# Sensing_current.net
KiCad netlist of a schematic drawn in Altium Designer
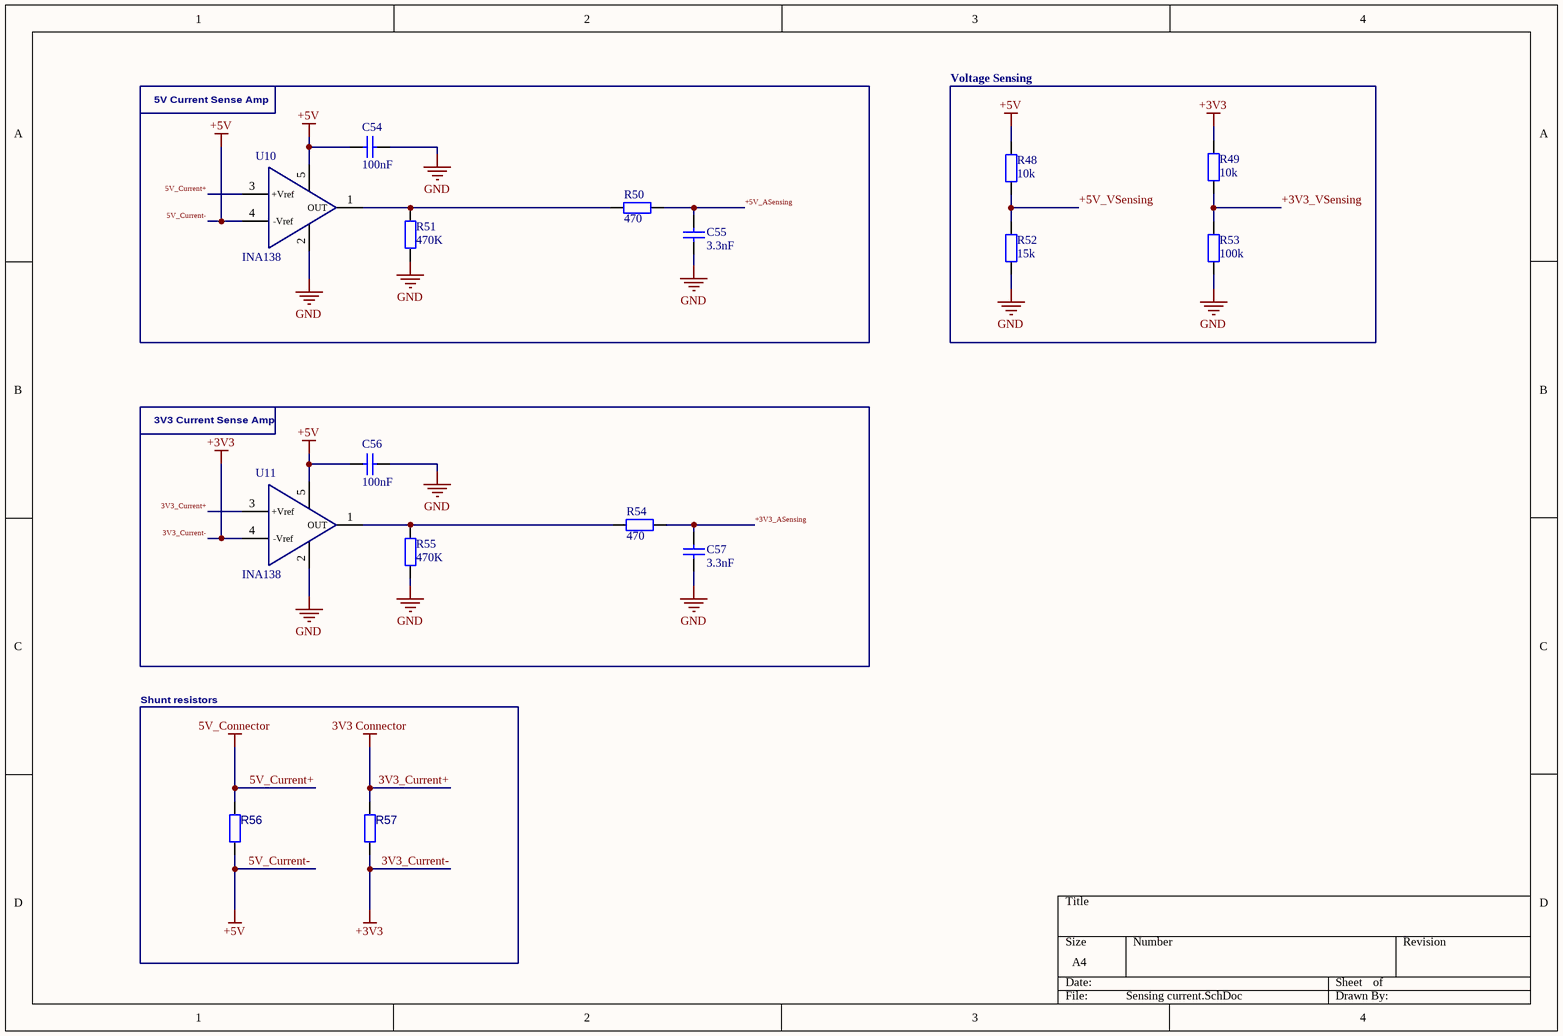
[diagram p0: Sensing current.SchDoc]

(export (version "E")
  (design (tool "Eeschema 10.0.6"))
  (components
    (comp (ref "C54")
      (value "100nF")
      (footprint "WCAP-CSGP_0603_L1.6W0.8H0.8_Reflow")
      (description "WCAP-CSGP Multilayer Ceramic Chip Capacitor, General Purpose, size 0603, X7R, 100nF, 25VDC")
      (fields
        (field (name "MANUFACTURER") "Wurth Elektronik")
        (field (name "MANUFACTURER PART NUMBER") "885012206071")
      )
      (libsource (lib "LEEM UPM") (part "885012209047R"))
    )
    (comp (ref "C55")
      (value "3.3nF")
      (footprint "WCAP-CSGP_0603_L1.6W0.8H0.8_Reflow")
      (description "WCAP-CSGP Multilayer Ceramic Chip Capacitor, General Purpose, size 0603, X7R, 3.3nF, 25VDC")
      (fields
        (field (name "MANUFACTURER") "Wurth Elektronik")
        (field (name "MANUFACTURER PART NUMBER") "885012206062")
      )
      (libsource (lib "LEEM UPM") (part "885012209047R"))
    )
    (comp (ref "C56")
      (value "100nF")
      (footprint "WCAP-CSGP_0603_L1.6W0.8H0.8_Reflow")
      (description "WCAP-CSGP Multilayer Ceramic Chip Capacitor, General Purpose, size 0603, X7R, 100nF, 25VDC")
      (fields
        (field (name "MANUFACTURER") "Wurth Elektronik")
        (field (name "MANUFACTURER PART NUMBER") "885012206071")
      )
      (libsource (lib "LEEM UPM") (part "885012209047R"))
    )
    (comp (ref "C57")
      (value "3.3nF")
      (footprint "WCAP-CSGP_0603_L1.6W0.8H0.8_Reflow")
      (description "WCAP-CSGP Multilayer Ceramic Chip Capacitor, General Purpose, size 0603, X7R, 3.3nF, 25VDC")
      (fields
        (field (name "MANUFACTURER") "Wurth Elektronik")
        (field (name "MANUFACTURER PART NUMBER") "885012206062")
      )
      (libsource (lib "LEEM UPM") (part "885012209047R"))
    )
    (comp (ref "R48")
      (value "10k")
      (footprint "WRIS-RSKS_0603_Reflow")
      (description "WRIS-RSKS Thick Film Resistor, size 0603, 10000Ohm, 100mW")
      (fields
        (field (name "MANUFACTURER") "Wurth Elektronik")
        (field (name "MANUFACTURER PART NUMBER") "560112116005")
      )
      (libsource (lib "LEEM UPM") (part "560112140010"))
    )
    (comp (ref "R49")
      (value "10k")
      (footprint "WRIS-RSKS_0603_Reflow")
      (description "WRIS-RSKS Thick Film Resistor, size 0603, 10000Ohm, 100mW")
      (fields
        (field (name "MANUFACTURER") "Wurth Elektronik")
        (field (name "MANUFACTURER PART NUMBER") "560112116005")
      )
      (libsource (lib "LEEM UPM") (part "560112140010"))
    )
    (comp (ref "R50")
      (value "470")
      (footprint "WRIS-RSKS_0603_Reflow")
      (description "WRIS-RSKS Thick Film Resistor, size 0603, 470Ohm, 100mW")
      (fields
        (field (name "MANUFACTURER") "Wurth Elektronik")
        (field (name "MANUFACTURER PART NUMBER") "560112116067")
      )
      (libsource (lib "") (part "560112140010_1"))
    )
    (comp (ref "R51")
      (value "470K")
      (footprint "WRIS-RSKS_0603_Reflow")
      (description "WRIS-RSKS Thick Film Resistor, size 0603, 470000Ohm, 100mW")
      (fields
        (field (name "MANUFACTURER") "Wurth Elektronik")
        (field (name "MANUFACTURER PART NUMBER") "560112116019")
      )
      (libsource (lib "LEEM UPM") (part "560112140010"))
    )
    (comp (ref "R52")
      (value "15k")
      (footprint "WRIS-RSKS_0603_Reflow")
      (description "WRIS-RSKS Thick Film Resistor, size 0603, 15000Ohm, 100mW")
      (fields
        (field (name "MANUFACTURER") "Wurth Elektronik")
        (field (name "MANUFACTURER PART NUMBER") "560112116035")
      )
      (libsource (lib "LEEM UPM") (part "560112140010"))
    )
    (comp (ref "R53")
      (value "100k")
      (footprint "WRIS-RSKS_0603_Reflow")
      (description "WRIS-RSKS Thick Film Resistor, size 0603, 100000Ohm, 100mW")
      (fields
        (field (name "MANUFACTURER PART NUMBER") "560112116004")
        (field (name "MANUFACTURER") "Wurth Elektronik")
      )
      (libsource (lib "LEEM UPM") (part "560112140010"))
    )
    (comp (ref "R54")
      (value "470")
      (footprint "WRIS-RSKS_0603_Reflow")
      (description "WRIS-RSKS Thick Film Resistor, size 0603, 470Ohm, 100mW")
      (fields
        (field (name "MANUFACTURER") "Wurth Elektronik")
        (field (name "MANUFACTURER PART NUMBER") "560112116067")
      )
      (libsource (lib "") (part "560112140010_1"))
    )
    (comp (ref "R55")
      (value "470K")
      (footprint "WRIS-RSKS_0603_Reflow")
      (description "WRIS-RSKS Thick Film Resistor, size 0603, 470000Ohm, 100mW")
      (fields
        (field (name "MANUFACTURER") "Wurth Elektronik")
        (field (name "MANUFACTURER PART NUMBER") "560112116019")
      )
      (libsource (lib "LEEM UPM") (part "560112140010"))
    )
    (comp (ref "R56")
      (value "580070763010")
      (footprint "580070763010-Footprint-1")
      (description "Res, 0R01, 1%, 2W, Metal Foil, 0612 Rohs Compliant: Yes")
      (libsource (lib "LEEM UPM") (part "RES-2"))
    )
    (comp (ref "R57")
      (value "580070763010")
      (footprint "580070763010-Footprint-1")
      (description "Res, 0R01, 1%, 2W, Metal Foil, 0612 Rohs Compliant: Yes")
      (libsource (lib "LEEM UPM") (part "RES-2"))
    )
    (comp (ref "U10")
      (value "INA138")
      (footprint "INA138-Footprint-1")
      (description "Shunt Current Measure Amplifier")
      (fields
        (field (name "MANUFACTURER") "Texas Instruments")
        (field (name "MANUFACTURER PART NUMBER") "INA138NA/3K")
      )
      (libsource (lib "LEEM UPM") (part "INA138-Symbol-1"))
    )
    (comp (ref "U11")
      (value "INA138")
      (footprint "INA138-Footprint-1")
      (description "Shunt Current Measure Amplifier")
      (fields
        (field (name "MANUFACTURER") "Texas Instruments")
        (field (name "MANUFACTURER PART NUMBER") "INA138NA/3K")
      )
      (libsource (lib "LEEM UPM") (part "INA138-Symbol-1"))
    )
  )
  (nets
    (net (code "1") (name "+3V3") (class "Default")
      (node (ref "R49") (pin "2") (pinfunction "2_2") (pintype "passive"))
      (node (ref "R57") (pin "1") (pinfunction "1_1") (pintype "passive"))
      (node (ref "U11") (pin "4") (pinfunction "-Vref_4") (pintype "passive"))
    )
    (net (code "2") (name "+5V") (class "Default")
      (node (ref "C54") (pin "2") (pinfunction "2_2") (pintype "passive"))
      (node (ref "C56") (pin "2") (pinfunction "2_2") (pintype "passive"))
      (node (ref "R48") (pin "2") (pinfunction "2_2") (pintype "passive"))
      (node (ref "R56") (pin "1") (pinfunction "1_1") (pintype "passive"))
      (node (ref "U10") (pin "4") (pinfunction "-Vref_4") (pintype "passive"))
      (node (ref "U10") (pin "5") (pinfunction "V+_5") (pintype "passive"))
      (node (ref "U11") (pin "5") (pinfunction "V+_5") (pintype "passive"))
    )
    (net (code "3") (name "/+3V3_ASensing") (class "Default")
      (node (ref "C57") (pin "2") (pinfunction "2_2") (pintype "passive"))
      (node (ref "R54") (pin "1") (pinfunction "1_1") (pintype "passive"))
    )
    (net (code "4") (name "/+3V3_VSensing") (class "Default")
      (node (ref "R49") (pin "1") (pinfunction "1_1") (pintype "passive"))
      (node (ref "R53") (pin "2") (pinfunction "2_2") (pintype "passive"))
    )
    (net (code "5") (name "/+5V_ASensing") (class "Default")
      (node (ref "C55") (pin "2") (pinfunction "2_2") (pintype "passive"))
      (node (ref "R50") (pin "1") (pinfunction "1_1") (pintype "passive"))
    )
    (net (code "6") (name "/+5V_VSensing") (class "Default")
      (node (ref "R48") (pin "1") (pinfunction "1_1") (pintype "passive"))
      (node (ref "R52") (pin "2") (pinfunction "2_2") (pintype "passive"))
    )
    (net (code "7") (name "3V3 Connector") (class "Default")
      (node (ref "R57") (pin "2") (pinfunction "2_2") (pintype "passive"))
      (node (ref "U11") (pin "3") (pinfunction "+Vref_3") (pintype "passive"))
    )
    (net (code "8") (name "5V_Connector") (class "Default")
      (node (ref "R56") (pin "2") (pinfunction "2_2") (pintype "passive"))
      (node (ref "U10") (pin "3") (pinfunction "+Vref_3") (pintype "passive"))
    )
    (net (code "9") (name "GND") (class "Default")
      (node (ref "C54") (pin "1") (pinfunction "1_1") (pintype "passive"))
      (node (ref "C55") (pin "1") (pinfunction "1_1") (pintype "passive"))
      (node (ref "C56") (pin "1") (pinfunction "1_1") (pintype "passive"))
      (node (ref "C57") (pin "1") (pinfunction "1_1") (pintype "passive"))
      (node (ref "R51") (pin "1") (pinfunction "1_1") (pintype "passive"))
      (node (ref "R52") (pin "1") (pinfunction "1_1") (pintype "passive"))
      (node (ref "R53") (pin "1") (pinfunction "1_1") (pintype "passive"))
      (node (ref "R55") (pin "1") (pinfunction "1_1") (pintype "passive"))
      (node (ref "U10") (pin "2") (pinfunction "GND_2") (pintype "passive"))
      (node (ref "U11") (pin "2") (pinfunction "GND_2") (pintype "passive"))
    )
    (net (code "10") (name "Net-(U10-OUT)") (class "Default")
      (node (ref "R50") (pin "2") (pinfunction "2_2") (pintype "passive"))
      (node (ref "R51") (pin "2") (pinfunction "2_2") (pintype "passive"))
      (node (ref "U10") (pin "1") (pinfunction "OUT_1") (pintype "passive"))
    )
    (net (code "11") (name "Net-(U11-OUT)") (class "Default")
      (node (ref "R54") (pin "2") (pinfunction "2_2") (pintype "passive"))
      (node (ref "R55") (pin "2") (pinfunction "2_2") (pintype "passive"))
      (node (ref "U11") (pin "1") (pinfunction "OUT_1") (pintype "passive"))
    )
  )
)
